# CH340E-noUSB.net
KiCad netlist of a schematic drawn in EAGLE
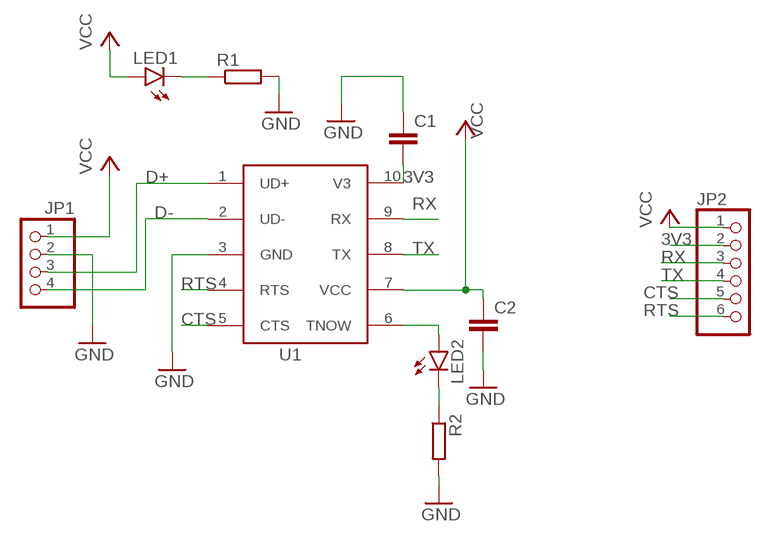
[diagram p0: schematic, sheet 1]

(export (version "E")
  (design (tool "Eeschema 10.0.6"))
  (components
    (comp (ref "C1")
      (value "C-EUC0603")
      (footprint "eagle-import:C0603")
      (libsource (lib "eagle-import") (part "C-EUC0603"))
    )
    (comp (ref "C2")
      (value "C-EUC0603")
      (footprint "eagle-import:C0603")
      (libsource (lib "eagle-import") (part "C-EUC0603"))
    )
    (comp (ref "JP1")
      (value "PINHD-1X4")
      (footprint "eagle-import:1X04")
      (libsource (lib "eagle-import") (part "PINHD-1X4"))
    )
    (comp (ref "JP2")
      (value "PINHD-1X6/90")
      (footprint "eagle-import:1X06_90")
      (libsource (lib "eagle-import") (part "PINHD-1X6/90"))
    )
    (comp (ref "LED1")
      (value "LEDCHIP-LED0603")
      (footprint "eagle-import:CHIP-LED0603")
      (libsource (lib "eagle-import") (part "LEDCHIP-LED0603"))
    )
    (comp (ref "LED2")
      (value "LEDCHIP-LED0603")
      (footprint "eagle-import:CHIP-LED0603")
      (libsource (lib "eagle-import") (part "LEDCHIP-LED0603"))
    )
    (comp (ref "R1")
      (value "R-EU_R0603")
      (footprint "eagle-import:R0603")
      (libsource (lib "eagle-import") (part "R-EU_R0603"))
    )
    (comp (ref "R2")
      (value "R-EU_R0603")
      (footprint "eagle-import:R0603")
      (libsource (lib "eagle-import") (part "R-EU_R0603"))
    )
    (comp (ref "U1")
      (value "CH340ESMD")
      (footprint "eagle-import:MSOP10")
      (libsource (lib "eagle-import") (part "CH340ESMD"))
    )
  )
  (nets
    (net (code "1") (name "/3V3") (class "Default")
      (node (ref "C1") (pin "2") (pinfunction "2_2") (pintype "passive"))
      (node (ref "JP2") (pin "2") (pinfunction "2_2") (pintype "passive"))
      (node (ref "U1") (pin "10") (pinfunction "V3_10") (pintype "power_in"))
    )
    (net (code "2") (name "/CTS") (class "Default")
      (node (ref "JP2") (pin "5") (pinfunction "5_5") (pintype "passive"))
      (node (ref "U1") (pin "5") (pinfunction "CTS_5") (pintype "input"))
    )
    (net (code "3") (name "/D+") (class "Default")
      (node (ref "JP1") (pin "3") (pinfunction "3_3") (pintype "passive"))
      (node (ref "U1") (pin "1") (pinfunction "UD+_1") (pintype "bidirectional"))
    )
    (net (code "4") (name "/D-") (class "Default")
      (node (ref "JP1") (pin "4") (pinfunction "4_4") (pintype "passive"))
      (node (ref "U1") (pin "2") (pinfunction "UD-_2") (pintype "bidirectional"))
    )
    (net (code "5") (name "/RTS") (class "Default")
      (node (ref "JP2") (pin "6") (pinfunction "6_6") (pintype "passive"))
      (node (ref "U1") (pin "4") (pinfunction "RTS_4") (pintype "output"))
    )
    (net (code "6") (name "/RX") (class "Default")
      (node (ref "JP2") (pin "3") (pinfunction "3_3") (pintype "passive"))
      (node (ref "U1") (pin "9") (pinfunction "RX_9") (pintype "input"))
    )
    (net (code "7") (name "/TX") (class "Default")
      (node (ref "JP2") (pin "4") (pinfunction "4_4") (pintype "passive"))
      (node (ref "U1") (pin "8") (pinfunction "TX_8") (pintype "output"))
    )
    (net (code "8") (name "GND") (class "Default")
      (node (ref "C1") (pin "1") (pinfunction "1_1") (pintype "passive"))
      (node (ref "C2") (pin "2") (pinfunction "2_2") (pintype "passive"))
      (node (ref "JP1") (pin "2") (pinfunction "2_2") (pintype "passive"))
      (node (ref "R1") (pin "2") (pinfunction "2_2") (pintype "passive"))
      (node (ref "R2") (pin "2") (pinfunction "2_2") (pintype "passive"))
      (node (ref "U1") (pin "3") (pinfunction "GND_3") (pintype "power_in"))
    )
    (net (code "9") (name "Net-(LED1-PadC)") (class "Default")
      (node (ref "LED1") (pin "C") (pinfunction "C_C") (pintype "passive"))
      (node (ref "R1") (pin "1") (pinfunction "1_1") (pintype "passive"))
    )
    (net (code "10") (name "Net-(LED2-PadC)") (class "Default")
      (node (ref "LED2") (pin "C") (pinfunction "C_C") (pintype "passive"))
      (node (ref "R2") (pin "1") (pinfunction "1_1") (pintype "passive"))
    )
    (net (code "11") (name "Net-(U1-TNOW)") (class "Default")
      (node (ref "LED2") (pin "A") (pinfunction "A_A") (pintype "passive"))
      (node (ref "U1") (pin "6") (pinfunction "TNOW_6") (pintype "output"))
    )
    (net (code "12") (name "VCC") (class "Default")
      (node (ref "C2") (pin "1") (pinfunction "1_1") (pintype "passive"))
      (node (ref "JP1") (pin "1") (pinfunction "1_1") (pintype "passive"))
      (node (ref "JP2") (pin "1") (pinfunction "1_1") (pintype "passive"))
      (node (ref "LED1") (pin "A") (pinfunction "A_A") (pintype "passive"))
      (node (ref "U1") (pin "7") (pinfunction "VCC_7") (pintype "power_in"))
    )
  )
)
